# design.net
KiCad netlist of a schematic drawn in EasyEDA
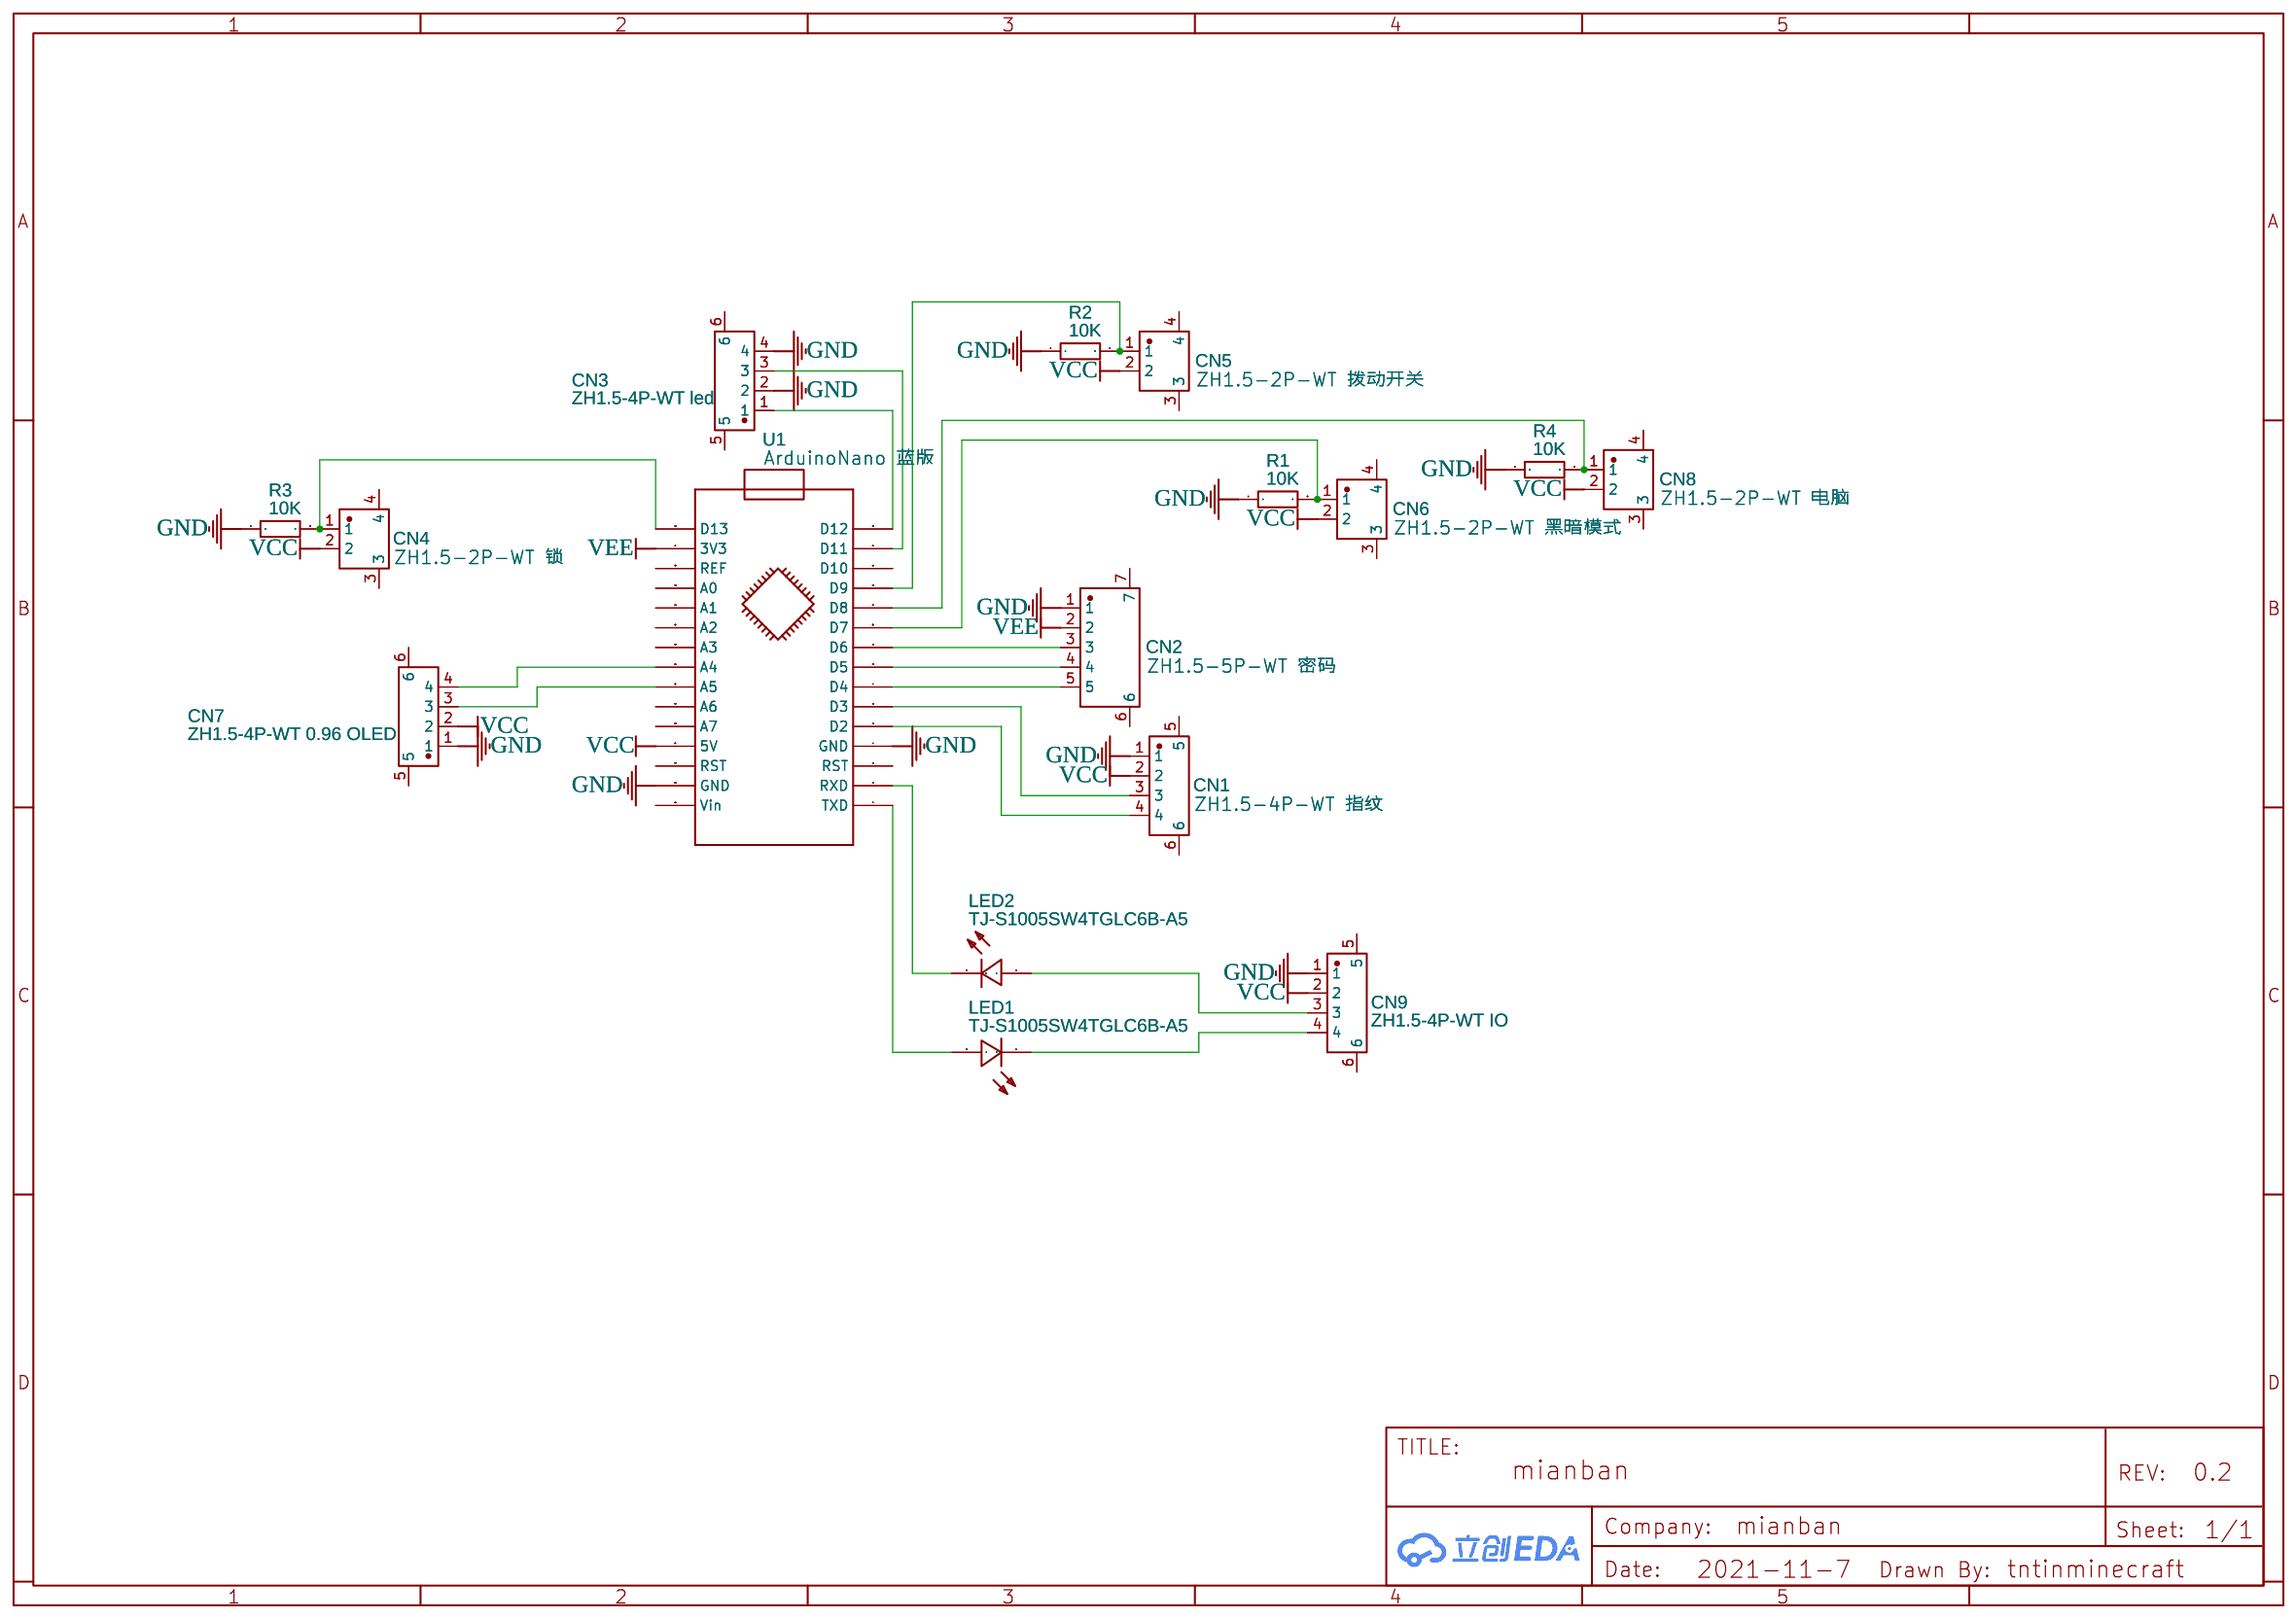
[diagram p0: schematic sheet]

(export (version "E")
  (design (tool "Eeschema 10.0.6"))
  (components
    (comp (ref "CN1")
      (value "ZH1.5-4P-WT 指纹")
      (fields
        (field (name "BOM_Manufacturer Part") "ZH1.5-4P-WT")
        (field (name "BOM_Supplier Part") "C722921")
      )
      (libsource (lib "") (part "ZH1.5-4P-WT"))
    )
    (comp (ref "CN2")
      (value "ZH1.5-5P-WT 密码")
      (fields
        (field (name "BOM_Manufacturer Part") "ZH1.5-5P-WT")
        (field (name "BOM_Supplier Part") "C722925")
      )
      (libsource (lib "") (part "ZH1.5-5P-WT"))
    )
    (comp (ref "CN3")
      (value "ZH1.5-4P-WT led")
      (fields
        (field (name "BOM_Manufacturer Part") "ZH1.5-4P-WT")
        (field (name "BOM_Supplier Part") "C722921")
      )
      (libsource (lib "") (part "ZH1.5-4P-WT_1"))
    )
    (comp (ref "CN4")
      (value "ZH1.5-2P-WT 锁")
      (fields
        (field (name "BOM_Manufacturer Part") "ZH1.5-2P-WT")
        (field (name "BOM_Supplier Part") "C722913")
      )
      (libsource (lib "") (part "ZH1.5-2P-WT"))
    )
    (comp (ref "CN5")
      (value "ZH1.5-2P-WT 拨动开关")
      (fields
        (field (name "BOM_Manufacturer Part") "ZH1.5-2P-WT")
        (field (name "BOM_Supplier Part") "C722913")
      )
      (libsource (lib "") (part "ZH1.5-2P-WT"))
    )
    (comp (ref "CN6")
      (value "ZH1.5-2P-WT 黑暗模式")
      (fields
        (field (name "BOM_Manufacturer Part") "ZH1.5-2P-WT")
        (field (name "BOM_Supplier Part") "C722913")
      )
      (libsource (lib "") (part "ZH1.5-2P-WT"))
    )
    (comp (ref "CN7")
      (value "ZH1.5-4P-WT 0.96 OLED")
      (fields
        (field (name "BOM_Manufacturer Part") "ZH1.5-4P-WT")
        (field (name "BOM_Supplier Part") "C722921")
      )
      (libsource (lib "") (part "ZH1.5-4P-WT_1"))
    )
    (comp (ref "CN8")
      (value "ZH1.5-2P-WT 电脑")
      (fields
        (field (name "BOM_Manufacturer Part") "ZH1.5-2P-WT")
        (field (name "BOM_Supplier Part") "C722913")
      )
      (libsource (lib "") (part "ZH1.5-2P-WT"))
    )
    (comp (ref "CN9")
      (value "ZH1.5-4P-WT IO")
      (fields
        (field (name "BOM_Manufacturer Part") "ZH1.5-4P-WT")
        (field (name "BOM_Supplier Part") "C722921")
      )
      (libsource (lib "") (part "ZH1.5-4P-WT"))
    )
    (comp (ref "LED1")
      (value "TJ-S1005SW4TGLC6B-A5")
      (fields (field (name "BOM_Supplier Part") "C273603"))
      (libsource (lib "") (part "TJ-S1005SW4TGLC6B-A5"))
    )
    (comp (ref "LED2")
      (value "TJ-S1005SW4TGLC6B-A5")
      (fields (field (name "BOM_Supplier Part") "C273603"))
      (libsource (lib "") (part "TJ-S1005SW4TGLC6B-A5_1"))
    )
    (comp (ref "R1")
      (value "10K")
      (fields
        (field (name "BOM_Manufacturer Part") "LE03WAJ0103T5E")
        (field (name "BOM_Supplier Part") "C81087")
      )
      (libsource (lib "") (part "LE03WAJ0103T5E"))
    )
    (comp (ref "R2")
      (value "10K")
      (fields
        (field (name "BOM_Manufacturer Part") "LE03WAJ0103T5E")
        (field (name "BOM_Supplier Part") "C81087")
      )
      (libsource (lib "") (part "LE03WAJ0103T5E"))
    )
    (comp (ref "R3")
      (value "10K")
      (fields
        (field (name "BOM_Manufacturer Part") "LE03WAJ0103T5E")
        (field (name "BOM_Supplier Part") "C81087")
      )
      (libsource (lib "") (part "LE03WAJ0103T5E"))
    )
    (comp (ref "R4")
      (value "10K")
      (fields
        (field (name "BOM_Manufacturer Part") "LE03WAJ0103T5E")
        (field (name "BOM_Supplier Part") "C81087")
      )
      (libsource (lib "") (part "LE03WAJ0103T5E"))
    )
    (comp (ref "U1")
      (value "ArduinoNano 蓝版")
      (fields (field (name "BOM_Manufacturer Part") "ArduinoNano"))
      (libsource (lib "") (part "ArduinoNano 蓝版"))
    )
  )
  (nets
    (net (code "1") (name "GND") (class "Default")
      (node (ref "CN1") (pin "1") (pinfunction "1_1") (pintype "unspecified"))
      (node (ref "CN2") (pin "1") (pinfunction "1_1") (pintype "unspecified"))
      (node (ref "CN3") (pin "2") (pinfunction "2_2") (pintype "unspecified"))
      (node (ref "CN3") (pin "4") (pinfunction "4_4") (pintype "unspecified"))
      (node (ref "CN7") (pin "1") (pinfunction "1_1") (pintype "unspecified"))
      (node (ref "CN9") (pin "1") (pinfunction "1_1") (pintype "unspecified"))
      (node (ref "R1") (pin "1") (pinfunction "1_1") (pintype "input"))
      (node (ref "R2") (pin "1") (pinfunction "1_1") (pintype "input"))
      (node (ref "R3") (pin "1") (pinfunction "1_1") (pintype "input"))
      (node (ref "R4") (pin "1") (pinfunction "1_1") (pintype "input"))
      (node (ref "U1") (pin "29") (pinfunction "GND_29") (pintype "unspecified"))
      (node (ref "U1") (pin "4") (pinfunction "GND_4") (pintype "unspecified"))
    )
    (net (code "2") (name "Net-(LED1-A)") (class "Default")
      (node (ref "LED1") (pin "2") (pinfunction "A_2") (pintype "unspecified"))
      (node (ref "U1") (pin "1") (pinfunction "TXD_1") (pintype "unspecified"))
    )
    (net (code "3") (name "Net-(LED1-C)") (class "Default")
      (node (ref "CN9") (pin "4") (pinfunction "4_4") (pintype "unspecified"))
      (node (ref "LED1") (pin "1") (pinfunction "C_1") (pintype "unspecified"))
    )
    (net (code "4") (name "Net-(LED2-A)") (class "Default")
      (node (ref "CN9") (pin "3") (pinfunction "3_3") (pintype "unspecified"))
      (node (ref "LED2") (pin "2") (pinfunction "A_2") (pintype "unspecified"))
    )
    (net (code "5") (name "Net-(LED2-C)") (class "Default")
      (node (ref "LED2") (pin "1") (pinfunction "C_1") (pintype "unspecified"))
      (node (ref "U1") (pin "2") (pinfunction "RXD_2") (pintype "unspecified"))
    )
    (net (code "6") (name "Net-(U1-A4)") (class "Default")
      (node (ref "CN7") (pin "4") (pinfunction "4_4") (pintype "unspecified"))
      (node (ref "U1") (pin "23") (pinfunction "A4_23") (pintype "unspecified"))
    )
    (net (code "7") (name "Net-(U1-A5)") (class "Default")
      (node (ref "CN7") (pin "3") (pinfunction "3_3") (pintype "unspecified"))
      (node (ref "U1") (pin "24") (pinfunction "A5_24") (pintype "unspecified"))
    )
    (net (code "8") (name "Net-(U1-D2)") (class "Default")
      (node (ref "CN1") (pin "4") (pinfunction "4_4") (pintype "unspecified"))
      (node (ref "U1") (pin "5") (pinfunction "D2_5") (pintype "unspecified"))
    )
    (net (code "9") (name "Net-(U1-D3)") (class "Default")
      (node (ref "CN1") (pin "3") (pinfunction "3_3") (pintype "unspecified"))
      (node (ref "U1") (pin "6") (pinfunction "D3_6") (pintype "unspecified"))
    )
    (net (code "10") (name "Net-(U1-D4)") (class "Default")
      (node (ref "CN2") (pin "5") (pinfunction "5_5") (pintype "unspecified"))
      (node (ref "U1") (pin "7") (pinfunction "D4_7") (pintype "unspecified"))
    )
    (net (code "11") (name "Net-(U1-D5)") (class "Default")
      (node (ref "CN2") (pin "4") (pinfunction "4_4") (pintype "unspecified"))
      (node (ref "U1") (pin "8") (pinfunction "D5_8") (pintype "unspecified"))
    )
    (net (code "12") (name "Net-(U1-D6)") (class "Default")
      (node (ref "CN2") (pin "3") (pinfunction "3_3") (pintype "unspecified"))
      (node (ref "U1") (pin "9") (pinfunction "D6_9") (pintype "unspecified"))
    )
    (net (code "13") (name "Net-(U1-D7)") (class "Default")
      (node (ref "CN6") (pin "1") (pinfunction "1_1") (pintype "unspecified"))
      (node (ref "R1") (pin "2") (pinfunction "2_2") (pintype "input"))
      (node (ref "U1") (pin "10") (pinfunction "D7_10") (pintype "unspecified"))
    )
    (net (code "14") (name "Net-(U1-D8)") (class "Default")
      (node (ref "CN8") (pin "1") (pinfunction "1_1") (pintype "unspecified"))
      (node (ref "R4") (pin "2") (pinfunction "2_2") (pintype "input"))
      (node (ref "U1") (pin "11") (pinfunction "D8_11") (pintype "unspecified"))
    )
    (net (code "15") (name "Net-(U1-D9)") (class "Default")
      (node (ref "CN5") (pin "1") (pinfunction "1_1") (pintype "unspecified"))
      (node (ref "R2") (pin "2") (pinfunction "2_2") (pintype "input"))
      (node (ref "U1") (pin "12") (pinfunction "D9_12") (pintype "unspecified"))
    )
    (net (code "16") (name "Net-(U1-D11)") (class "Default")
      (node (ref "CN3") (pin "3") (pinfunction "3_3") (pintype "unspecified"))
      (node (ref "U1") (pin "14") (pinfunction "D11_14") (pintype "unspecified"))
    )
    (net (code "17") (name "Net-(U1-D12)") (class "Default")
      (node (ref "CN3") (pin "1") (pinfunction "1_1") (pintype "unspecified"))
      (node (ref "U1") (pin "15") (pinfunction "D12_15") (pintype "unspecified"))
    )
    (net (code "18") (name "Net-(U1-D13)") (class "Default")
      (node (ref "CN4") (pin "1") (pinfunction "1_1") (pintype "unspecified"))
      (node (ref "R3") (pin "2") (pinfunction "2_2") (pintype "input"))
      (node (ref "U1") (pin "16") (pinfunction "D13_16") (pintype "unspecified"))
    )
    (net (code "19") (name "VCC") (class "Default")
      (node (ref "CN1") (pin "2") (pinfunction "2_2") (pintype "unspecified"))
      (node (ref "CN4") (pin "2") (pinfunction "2_2") (pintype "unspecified"))
      (node (ref "CN5") (pin "2") (pinfunction "2_2") (pintype "unspecified"))
      (node (ref "CN6") (pin "2") (pinfunction "2_2") (pintype "unspecified"))
      (node (ref "CN7") (pin "2") (pinfunction "2_2") (pintype "unspecified"))
      (node (ref "CN8") (pin "2") (pinfunction "2_2") (pintype "unspecified"))
      (node (ref "CN9") (pin "2") (pinfunction "2_2") (pintype "unspecified"))
      (node (ref "U1") (pin "27") (pinfunction "5V_27") (pintype "unspecified"))
    )
    (net (code "20") (name "VEE") (class "Default")
      (node (ref "CN2") (pin "2") (pinfunction "2_2") (pintype "unspecified"))
      (node (ref "U1") (pin "17") (pinfunction "3V3_17") (pintype "unspecified"))
    )
    (net (code "21") (name "unconnected-(CN1-Pad5)") (class "Default")
      (node (ref "CN1") (pin "5") (pinfunction "5_5") (pintype "unspecified"))
    )
    (net (code "22") (name "unconnected-(CN1-Pad6)") (class "Default")
      (node (ref "CN1") (pin "6") (pinfunction "6_6") (pintype "unspecified"))
    )
    (net (code "23") (name "unconnected-(CN2-Pad6)") (class "Default")
      (node (ref "CN2") (pin "6") (pinfunction "6_6") (pintype "unspecified"))
    )
    (net (code "24") (name "unconnected-(CN2-Pad7)") (class "Default")
      (node (ref "CN2") (pin "7") (pinfunction "7_7") (pintype "unspecified"))
    )
    (net (code "25") (name "unconnected-(CN3-Pad5)") (class "Default")
      (node (ref "CN3") (pin "5") (pinfunction "5_5") (pintype "unspecified"))
    )
    (net (code "26") (name "unconnected-(CN3-Pad6)") (class "Default")
      (node (ref "CN3") (pin "6") (pinfunction "6_6") (pintype "unspecified"))
    )
    (net (code "27") (name "unconnected-(CN4-Pad3)") (class "Default")
      (node (ref "CN4") (pin "3") (pinfunction "3_3") (pintype "unspecified"))
    )
    (net (code "28") (name "unconnected-(CN4-Pad4)") (class "Default")
      (node (ref "CN4") (pin "4") (pinfunction "4_4") (pintype "unspecified"))
    )
    (net (code "29") (name "unconnected-(CN5-Pad3)") (class "Default")
      (node (ref "CN5") (pin "3") (pinfunction "3_3") (pintype "unspecified"))
    )
    (net (code "30") (name "unconnected-(CN5-Pad4)") (class "Default")
      (node (ref "CN5") (pin "4") (pinfunction "4_4") (pintype "unspecified"))
    )
    (net (code "31") (name "unconnected-(CN6-Pad3)") (class "Default")
      (node (ref "CN6") (pin "3") (pinfunction "3_3") (pintype "unspecified"))
    )
    (net (code "32") (name "unconnected-(CN6-Pad4)") (class "Default")
      (node (ref "CN6") (pin "4") (pinfunction "4_4") (pintype "unspecified"))
    )
    (net (code "33") (name "unconnected-(CN7-Pad5)") (class "Default")
      (node (ref "CN7") (pin "5") (pinfunction "5_5") (pintype "unspecified"))
    )
    (net (code "34") (name "unconnected-(CN7-Pad6)") (class "Default")
      (node (ref "CN7") (pin "6") (pinfunction "6_6") (pintype "unspecified"))
    )
    (net (code "35") (name "unconnected-(CN8-Pad3)") (class "Default")
      (node (ref "CN8") (pin "3") (pinfunction "3_3") (pintype "unspecified"))
    )
    (net (code "36") (name "unconnected-(CN8-Pad4)") (class "Default")
      (node (ref "CN8") (pin "4") (pinfunction "4_4") (pintype "unspecified"))
    )
    (net (code "37") (name "unconnected-(CN9-Pad5)") (class "Default")
      (node (ref "CN9") (pin "5") (pinfunction "5_5") (pintype "unspecified"))
    )
    (net (code "38") (name "unconnected-(CN9-Pad6)") (class "Default")
      (node (ref "CN9") (pin "6") (pinfunction "6_6") (pintype "unspecified"))
    )
    (net (code "39") (name "unconnected-(U1-A0-Pad19)") (class "Default")
      (node (ref "U1") (pin "19") (pinfunction "A0_19") (pintype "unspecified"))
    )
    (net (code "40") (name "unconnected-(U1-A1-Pad20)") (class "Default")
      (node (ref "U1") (pin "20") (pinfunction "A1_20") (pintype "unspecified"))
    )
    (net (code "41") (name "unconnected-(U1-A2-Pad21)") (class "Default")
      (node (ref "U1") (pin "21") (pinfunction "A2_21") (pintype "unspecified"))
    )
    (net (code "42") (name "unconnected-(U1-A3-Pad22)") (class "Default")
      (node (ref "U1") (pin "22") (pinfunction "A3_22") (pintype "unspecified"))
    )
    (net (code "43") (name "unconnected-(U1-A6-Pad25)") (class "Default")
      (node (ref "U1") (pin "25") (pinfunction "A6_25") (pintype "unspecified"))
    )
    (net (code "44") (name "unconnected-(U1-A7-Pad26)") (class "Default")
      (node (ref "U1") (pin "26") (pinfunction "A7_26") (pintype "unspecified"))
    )
    (net (code "45") (name "unconnected-(U1-D10-Pad13)") (class "Default")
      (node (ref "U1") (pin "13") (pinfunction "D10_13") (pintype "unspecified"))
    )
    (net (code "46") (name "unconnected-(U1-REF-Pad18)") (class "Default")
      (node (ref "U1") (pin "18") (pinfunction "REF_18") (pintype "unspecified"))
    )
    (net (code "47") (name "unconnected-(U1-RST-Pad3)") (class "Default")
      (node (ref "U1") (pin "3") (pinfunction "RST_3") (pintype "unspecified"))
    )
    (net (code "48") (name "unconnected-(U1-RST-Pad28)") (class "Default")
      (node (ref "U1") (pin "28") (pinfunction "RST_28") (pintype "unspecified"))
    )
    (net (code "49") (name "unconnected-(U1-Vin-Pad30)") (class "Default")
      (node (ref "U1") (pin "30") (pinfunction "Vin_30") (pintype "unspecified"))
    )
  )
)
